# emitter_-_Copy.net
KiCad netlist of a schematic drawn in EAGLE
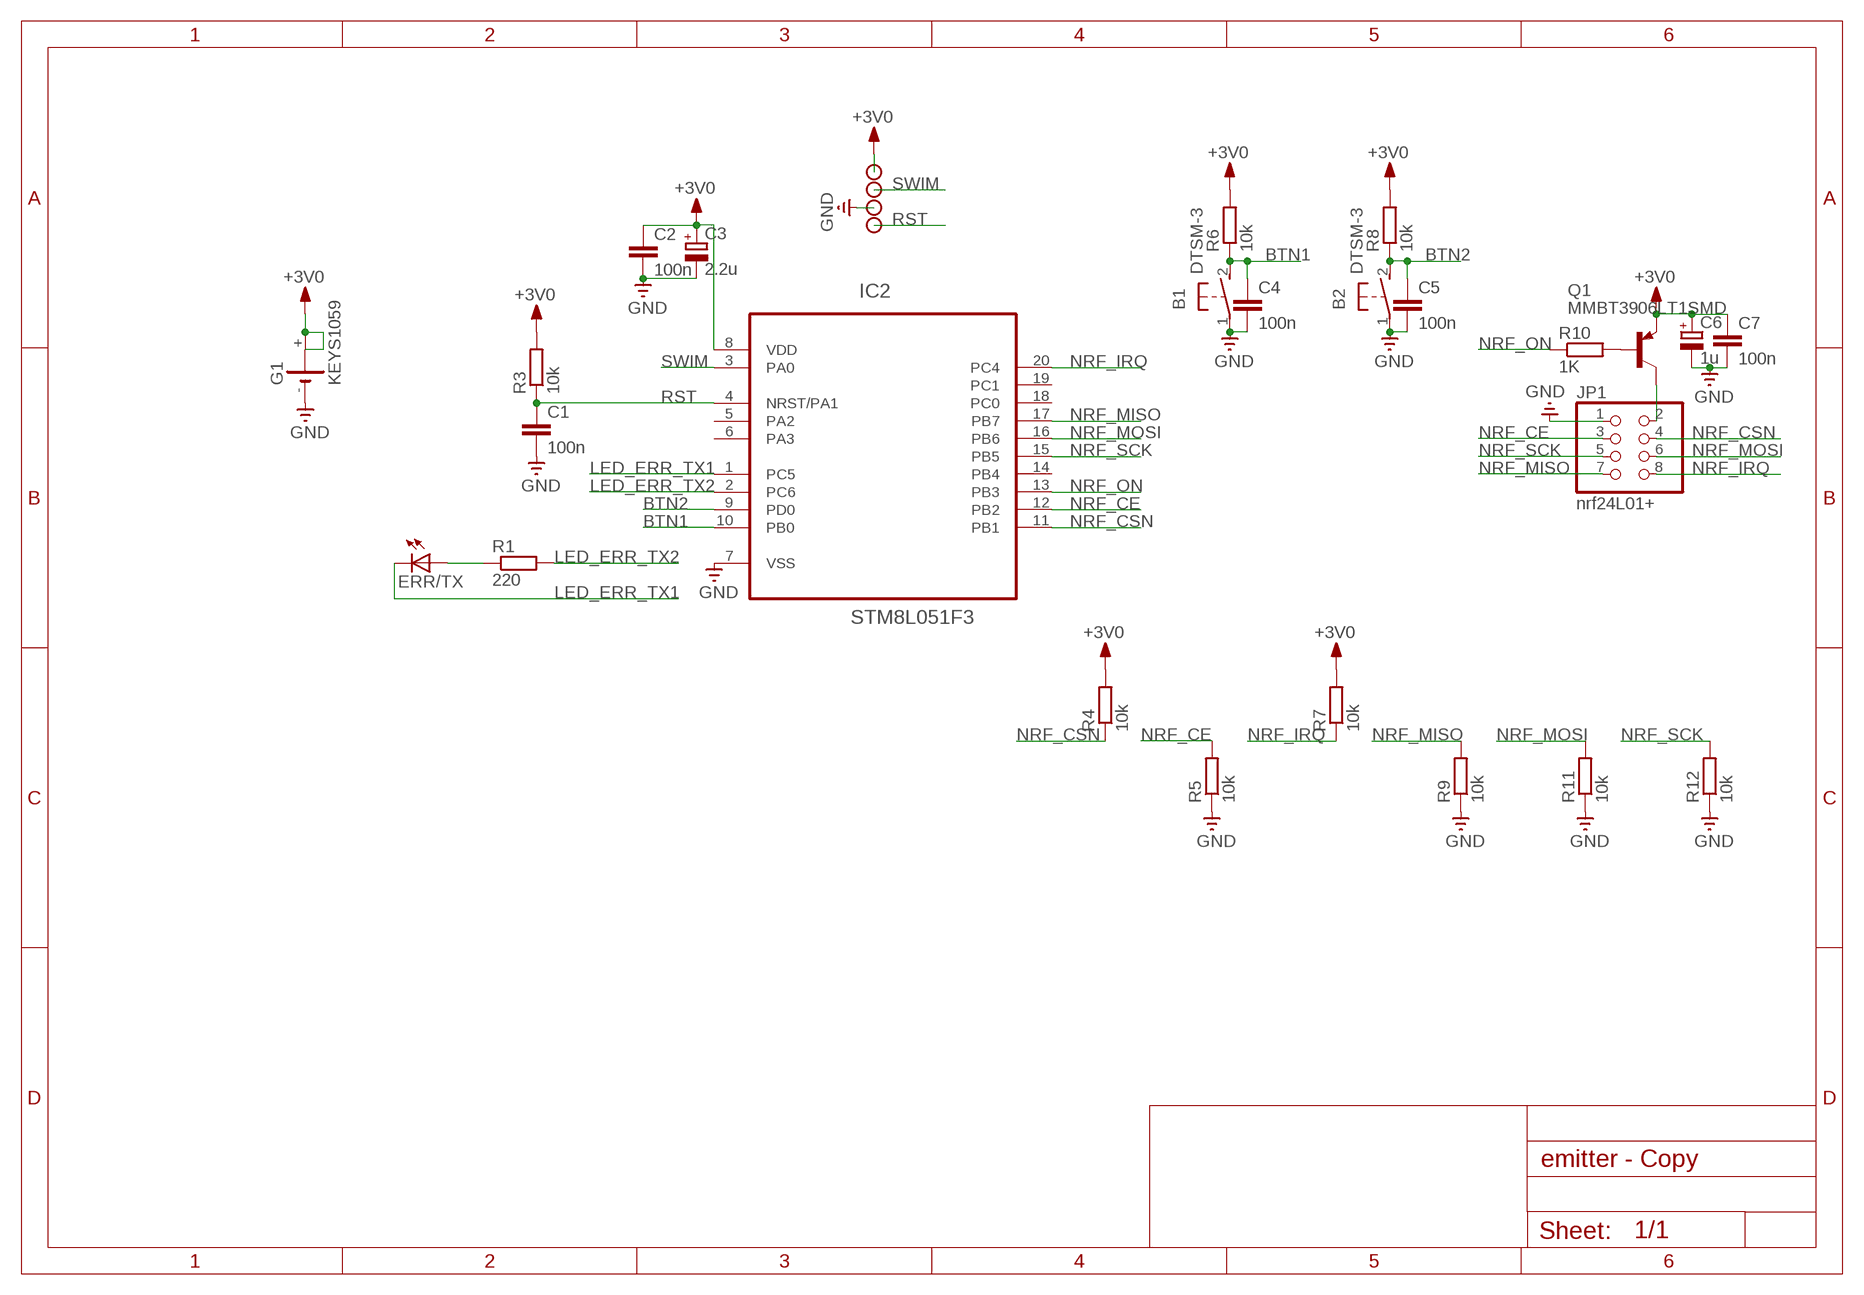
[diagram p0: schematic, sheet 1]

(export (version "E")
  (design (tool "Eeschema 10.0.6"))
  (components
    (comp (ref "B1")
      (value "DTSM-3")
      (footprint "eagle-import:DTSM-3")
      (libsource (lib "eagle-import") (part "DTSM-3"))
    )
    (comp (ref "B2")
      (value "DTSM-3")
      (footprint "eagle-import:DTSM-3")
      (libsource (lib "eagle-import") (part "DTSM-3"))
    )
    (comp (ref "C1")
      (value "100n")
      (footprint "eagle-import:C0603K")
      (libsource (lib "eagle-import") (part "C-EUC0603K"))
    )
    (comp (ref "C2")
      (value "100n")
      (footprint "eagle-import:C0603K")
      (libsource (lib "eagle-import") (part "C-EUC0603K"))
    )
    (comp (ref "C3")
      (value "2.2u")
      (footprint "eagle-import:SMC_A")
      (libsource (lib "eagle-import") (part "CPOL-EUSMCA"))
    )
    (comp (ref "C4")
      (value "100n")
      (footprint "eagle-import:C0603K")
      (libsource (lib "eagle-import") (part "C-EUC0603K"))
    )
    (comp (ref "C5")
      (value "100n")
      (footprint "eagle-import:C0603K")
      (libsource (lib "eagle-import") (part "C-EUC0603K"))
    )
    (comp (ref "C6")
      (value "1u")
      (footprint "eagle-import:SMC_A")
      (libsource (lib "eagle-import") (part "CPOL-EUSMCA"))
    )
    (comp (ref "C7")
      (value "100n")
      (footprint "eagle-import:C0603K")
      (libsource (lib "eagle-import") (part "C-EUC0603K"))
    )
    (comp (ref "ERR/TX")
      (value "LED3MM")
      (footprint "eagle-import:LED3MM")
      (libsource (lib "eagle-import") (part "LED3MM"))
    )
    (comp (ref "G1")
      (value "KEYS1059")
      (footprint "eagle-import:KEYS1059")
      (libsource (lib "eagle-import") (part "KEYS1059"))
    )
    (comp (ref "IC2")
      (value "STM8L051F3")
      (footprint "eagle-import:TSSOP20")
      (libsource (lib "eagle-import") (part "STM8L051F3"))
    )
    (comp (ref "JP1")
      (value "nrf24L01+")
      (footprint "eagle-import:2X04")
      (libsource (lib "eagle-import") (part "PINHD-2X4"))
    )
    (comp (ref "Q1")
      (value "MMBT3906LT1SMD")
      (footprint "eagle-import:SOT23-BEC")
      (libsource (lib "eagle-import") (part "MMBT3906SMDLT1"))
    )
    (comp (ref "R1")
      (value "220")
      (footprint "eagle-import:R0603")
      (libsource (lib "eagle-import") (part "R-EU_R0603"))
    )
    (comp (ref "R3")
      (value "10k")
      (footprint "eagle-import:R0603")
      (libsource (lib "eagle-import") (part "R-EU_R0603"))
    )
    (comp (ref "R4")
      (value "10k")
      (footprint "eagle-import:R0603")
      (libsource (lib "eagle-import") (part "R-EU_R0603"))
    )
    (comp (ref "R5")
      (value "10k")
      (footprint "eagle-import:R0603")
      (libsource (lib "eagle-import") (part "R-EU_R0603"))
    )
    (comp (ref "R6")
      (value "10k")
      (footprint "eagle-import:R0603")
      (libsource (lib "eagle-import") (part "R-EU_R0603"))
    )
    (comp (ref "R7")
      (value "10k")
      (footprint "eagle-import:R0603")
      (libsource (lib "eagle-import") (part "R-EU_R0603"))
    )
    (comp (ref "R8")
      (value "10k")
      (footprint "eagle-import:R0603")
      (libsource (lib "eagle-import") (part "R-EU_R0603"))
    )
    (comp (ref "R9")
      (value "10k")
      (footprint "eagle-import:R0603")
      (libsource (lib "eagle-import") (part "R-EU_R0603"))
    )
    (comp (ref "R10")
      (value "1K")
      (footprint "eagle-import:R0603")
      (libsource (lib "eagle-import") (part "R-EU_R0603"))
    )
    (comp (ref "R11")
      (value "10k")
      (footprint "eagle-import:R0603")
      (libsource (lib "eagle-import") (part "R-EU_R0603"))
    )
    (comp (ref "R12")
      (value "10k")
      (footprint "eagle-import:R0603")
      (libsource (lib "eagle-import") (part "R-EU_R0603"))
    )
    (comp (ref "SIG_+3V1")
      (value "CON_PAD")
      (footprint "eagle-import:SMD_PAD")
      (libsource (lib "eagle-import") (part "CON_PAD"))
    )
    (comp (ref "SIG_GND")
      (value "CON_PAD")
      (footprint "eagle-import:SMD_PAD")
      (libsource (lib "eagle-import") (part "CON_PAD"))
    )
    (comp (ref "SIG_RST")
      (value "CON_PAD")
      (footprint "eagle-import:SMD_PAD")
      (libsource (lib "eagle-import") (part "CON_PAD"))
    )
    (comp (ref "SIG_SWIM")
      (value "CON_PAD")
      (footprint "eagle-import:SMD_PAD")
      (libsource (lib "eagle-import") (part "CON_PAD"))
    )
  )
  (nets
    (net (code "1") (name "+3V0") (class "Default")
      (node (ref "C2") (pin "1") (pinfunction "1_1") (pintype "passive"))
      (node (ref "C3") (pin "+") (pinfunction "+_+") (pintype "passive"))
      (node (ref "C6") (pin "+") (pinfunction "+_+") (pintype "passive"))
      (node (ref "C7") (pin "1") (pinfunction "1_1") (pintype "passive"))
      (node (ref "G1") (pin "+") (pinfunction "+_+") (pintype "passive"))
      (node (ref "G1") (pin "@+") (pinfunction "+_@+") (pintype "passive"))
      (node (ref "IC2") (pin "8") (pinfunction "VDD_8") (pintype "power_in"))
      (node (ref "Q1") (pin "E") (pinfunction "E_E") (pintype "passive"))
      (node (ref "R3") (pin "2") (pinfunction "2_2") (pintype "passive"))
      (node (ref "R4") (pin "2") (pinfunction "2_2") (pintype "passive"))
      (node (ref "R6") (pin "2") (pinfunction "2_2") (pintype "passive"))
      (node (ref "R7") (pin "2") (pinfunction "2_2") (pintype "passive"))
      (node (ref "R8") (pin "2") (pinfunction "2_2") (pintype "passive"))
      (node (ref "SIG_+3V1") (pin "P$1") (pinfunction "P$1_P$1") (pintype "bidirectional"))
    )
    (net (code "2") (name "/BTN1") (class "Default")
      (node (ref "B1") (pin "2") (pinfunction "2_2") (pintype "passive"))
      (node (ref "C4") (pin "1") (pinfunction "1_1") (pintype "passive"))
      (node (ref "IC2") (pin "10") (pinfunction "PB0_10") (pintype "bidirectional"))
      (node (ref "R6") (pin "1") (pinfunction "1_1") (pintype "passive"))
    )
    (net (code "3") (name "/BTN2") (class "Default")
      (node (ref "B2") (pin "2") (pinfunction "2_2") (pintype "passive"))
      (node (ref "C5") (pin "1") (pinfunction "1_1") (pintype "passive"))
      (node (ref "IC2") (pin "9") (pinfunction "PD0_9") (pintype "bidirectional"))
      (node (ref "R8") (pin "1") (pinfunction "1_1") (pintype "passive"))
    )
    (net (code "4") (name "/LED_ERR_TX1") (class "Default")
      (node (ref "ERR/TX") (pin "K") (pinfunction "C_K") (pintype "passive"))
      (node (ref "IC2") (pin "1") (pinfunction "PC5_1") (pintype "bidirectional"))
    )
    (net (code "5") (name "/LED_ERR_TX2") (class "Default")
      (node (ref "IC2") (pin "2") (pinfunction "PC6_2") (pintype "bidirectional"))
      (node (ref "R1") (pin "2") (pinfunction "2_2") (pintype "passive"))
    )
    (net (code "6") (name "/NRF_CE") (class "Default")
      (node (ref "IC2") (pin "12") (pinfunction "PB2_12") (pintype "bidirectional"))
      (node (ref "JP1") (pin "3") (pinfunction "3_3") (pintype "passive"))
      (node (ref "R5") (pin "2") (pinfunction "2_2") (pintype "passive"))
    )
    (net (code "7") (name "/NRF_CSN") (class "Default")
      (node (ref "IC2") (pin "11") (pinfunction "PB1_11") (pintype "bidirectional"))
      (node (ref "JP1") (pin "4") (pinfunction "4_4") (pintype "passive"))
      (node (ref "R4") (pin "1") (pinfunction "1_1") (pintype "passive"))
    )
    (net (code "8") (name "/NRF_IRQ") (class "Default")
      (node (ref "IC2") (pin "20") (pinfunction "PC4_20") (pintype "bidirectional"))
      (node (ref "JP1") (pin "8") (pinfunction "8_8") (pintype "passive"))
      (node (ref "R7") (pin "1") (pinfunction "1_1") (pintype "passive"))
    )
    (net (code "9") (name "/NRF_MISO") (class "Default")
      (node (ref "IC2") (pin "17") (pinfunction "PB7_17") (pintype "bidirectional"))
      (node (ref "JP1") (pin "7") (pinfunction "7_7") (pintype "passive"))
      (node (ref "R9") (pin "2") (pinfunction "2_2") (pintype "passive"))
    )
    (net (code "10") (name "/NRF_MOSI") (class "Default")
      (node (ref "IC2") (pin "16") (pinfunction "PB6_16") (pintype "bidirectional"))
      (node (ref "JP1") (pin "6") (pinfunction "6_6") (pintype "passive"))
      (node (ref "R11") (pin "2") (pinfunction "2_2") (pintype "passive"))
    )
    (net (code "11") (name "/NRF_ON") (class "Default")
      (node (ref "IC2") (pin "13") (pinfunction "PB3_13") (pintype "bidirectional"))
      (node (ref "R10") (pin "1") (pinfunction "1_1") (pintype "passive"))
    )
    (net (code "12") (name "/NRF_SCK") (class "Default")
      (node (ref "IC2") (pin "15") (pinfunction "PB5_15") (pintype "bidirectional"))
      (node (ref "JP1") (pin "5") (pinfunction "5_5") (pintype "passive"))
      (node (ref "R12") (pin "2") (pinfunction "2_2") (pintype "passive"))
    )
    (net (code "13") (name "/RST") (class "Default")
      (node (ref "C1") (pin "1") (pinfunction "1_1") (pintype "passive"))
      (node (ref "IC2") (pin "4") (pinfunction "NRST/PA1_4") (pintype "bidirectional"))
      (node (ref "R3") (pin "1") (pinfunction "1_1") (pintype "passive"))
      (node (ref "SIG_RST") (pin "P$1") (pinfunction "P$1_P$1") (pintype "bidirectional"))
    )
    (net (code "14") (name "/SWIM") (class "Default")
      (node (ref "IC2") (pin "3") (pinfunction "PA0_3") (pintype "power_in"))
      (node (ref "SIG_SWIM") (pin "P$1") (pinfunction "P$1_P$1") (pintype "bidirectional"))
    )
    (net (code "15") (name "GND") (class "Default")
      (node (ref "B1") (pin "1") (pinfunction "1_1") (pintype "passive"))
      (node (ref "B2") (pin "1") (pinfunction "1_1") (pintype "passive"))
      (node (ref "C1") (pin "2") (pinfunction "2_2") (pintype "passive"))
      (node (ref "C2") (pin "2") (pinfunction "2_2") (pintype "passive"))
      (node (ref "C3") (pin "-") (pinfunction "-_-") (pintype "passive"))
      (node (ref "C4") (pin "2") (pinfunction "2_2") (pintype "passive"))
      (node (ref "C5") (pin "2") (pinfunction "2_2") (pintype "passive"))
      (node (ref "C6") (pin "-") (pinfunction "-_-") (pintype "passive"))
      (node (ref "C7") (pin "2") (pinfunction "2_2") (pintype "passive"))
      (node (ref "G1") (pin "-") (pinfunction "-_-") (pintype "passive"))
      (node (ref "IC2") (pin "7") (pinfunction "VSS_7") (pintype "power_in"))
      (node (ref "JP1") (pin "1") (pinfunction "1_1") (pintype "passive"))
      (node (ref "R11") (pin "1") (pinfunction "1_1") (pintype "passive"))
      (node (ref "R12") (pin "1") (pinfunction "1_1") (pintype "passive"))
      (node (ref "R5") (pin "1") (pinfunction "1_1") (pintype "passive"))
      (node (ref "R9") (pin "1") (pinfunction "1_1") (pintype "passive"))
      (node (ref "SIG_GND") (pin "P$1") (pinfunction "P$1_P$1") (pintype "bidirectional"))
    )
    (net (code "16") (name "Net-(ERR/TX-PadA)") (class "Default")
      (node (ref "ERR/TX") (pin "A") (pinfunction "A_A") (pintype "passive"))
      (node (ref "R1") (pin "1") (pinfunction "1_1") (pintype "passive"))
    )
    (net (code "17") (name "Net-(JP1-Pad2)") (class "Default")
      (node (ref "JP1") (pin "2") (pinfunction "2_2") (pintype "passive"))
      (node (ref "Q1") (pin "C") (pinfunction "C_C") (pintype "passive"))
    )
    (net (code "18") (name "Net-(Q1-PadB)") (class "Default")
      (node (ref "Q1") (pin "B") (pinfunction "B_B") (pintype "passive"))
      (node (ref "R10") (pin "2") (pinfunction "2_2") (pintype "passive"))
    )
    (net (code "19") (name "unconnected-(IC2-PA2-Pad5)") (class "Default")
      (node (ref "IC2") (pin "5") (pinfunction "PA2_5") (pintype "bidirectional"))
    )
    (net (code "20") (name "unconnected-(IC2-PA3-Pad6)") (class "Default")
      (node (ref "IC2") (pin "6") (pinfunction "PA3_6") (pintype "bidirectional"))
    )
    (net (code "21") (name "unconnected-(IC2-PB4-Pad14)") (class "Default")
      (node (ref "IC2") (pin "14") (pinfunction "PB4_14") (pintype "bidirectional"))
    )
    (net (code "22") (name "unconnected-(IC2-PC0-Pad18)") (class "Default")
      (node (ref "IC2") (pin "18") (pinfunction "PC0_18") (pintype "bidirectional"))
    )
    (net (code "23") (name "unconnected-(IC2-PC1-Pad19)") (class "Default")
      (node (ref "IC2") (pin "19") (pinfunction "PC1_19") (pintype "bidirectional"))
    )
  )
)
